# dual_encoder_shield_3v.net
KiCad netlist of a schematic drawn in EAGLE
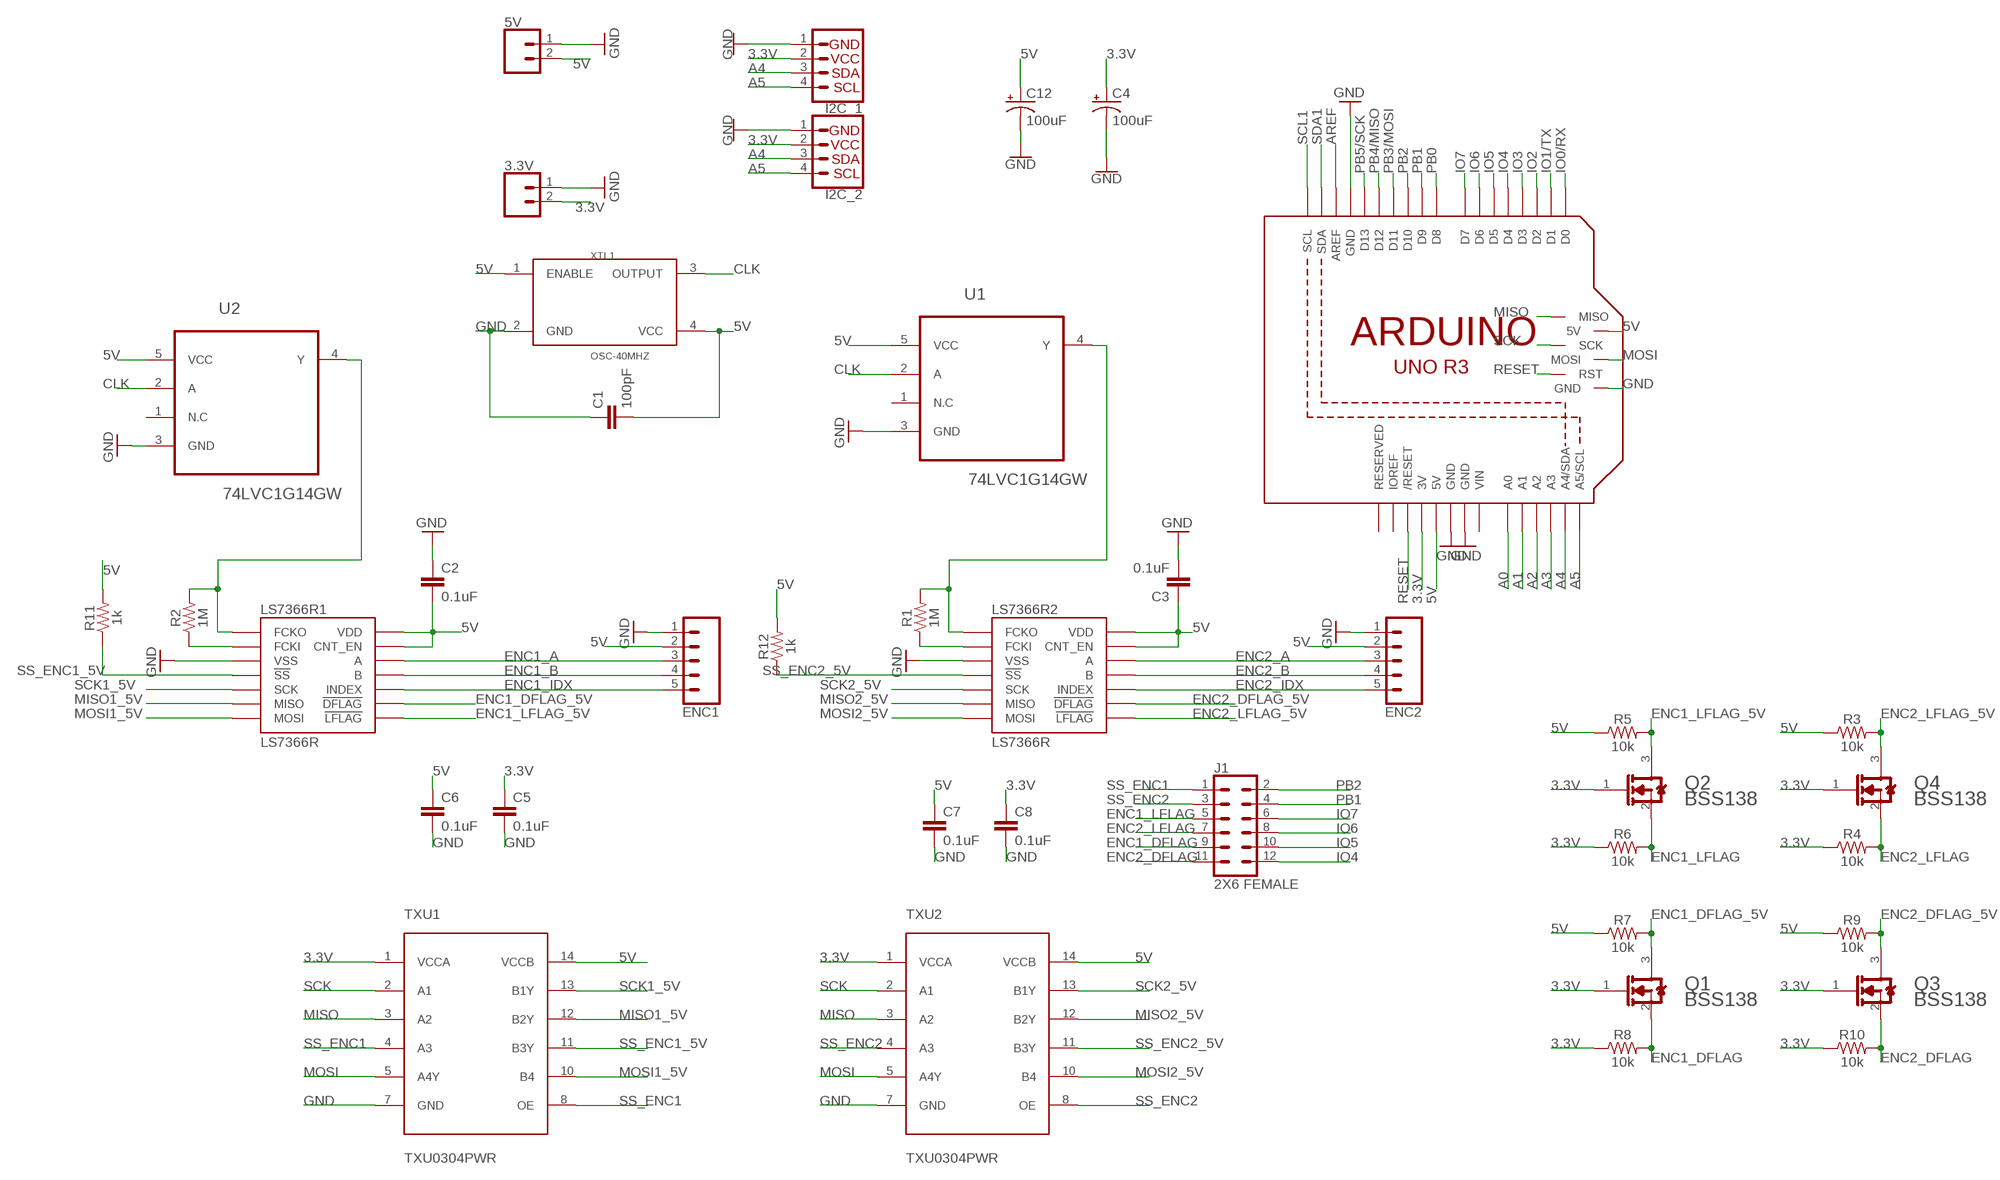
[diagram p0: schematic, sheet 1]

(export (version "E")
  (design (tool "Eeschema 10.0.6"))
  (components
    (comp (ref "3.3V")
      (value "CONN_02-JST-2MM-SMT")
      (footprint "eagle-import:JST-2-SMD")
      (libsource (lib "eagle-import") (part "CONN_02-JST-2MM-SMT"))
    )
    (comp (ref "5V")
      (value "CONN_02-JST-2MM-SMT")
      (footprint "eagle-import:JST-2-SMD")
      (libsource (lib "eagle-import") (part "CONN_02-JST-2MM-SMT"))
    )
    (comp (ref "C1")
      (value "100pF")
      (footprint "eagle-import:0603")
      (libsource (lib "eagle-import") (part "100PF-0603-50V-5%"))
    )
    (comp (ref "C2")
      (value "0.1uF")
      (footprint "eagle-import:0603")
      (libsource (lib "eagle-import") (part "0.1UF-0603-25V-5%"))
    )
    (comp (ref "C3")
      (value "0.1uF")
      (footprint "eagle-import:0603")
      (libsource (lib "eagle-import") (part "0.1UF-0603-25V-5%"))
    )
    (comp (ref "C4")
      (value "100uF")
      (footprint "eagle-import:PANASONIC_D")
      (libsource (lib "eagle-import") (part "100UF-POLAR-25V-20%(ELEC)"))
    )
    (comp (ref "C5")
      (value "0.1uF")
      (footprint "eagle-import:0603")
      (libsource (lib "eagle-import") (part "0.1UF-0603-25V-5%"))
    )
    (comp (ref "C6")
      (value "0.1uF")
      (footprint "eagle-import:0603")
      (libsource (lib "eagle-import") (part "0.1UF-0603-25V-5%"))
    )
    (comp (ref "C7")
      (value "0.1uF")
      (footprint "eagle-import:0603")
      (libsource (lib "eagle-import") (part "0.1UF-0603-25V-5%"))
    )
    (comp (ref "C8")
      (value "0.1uF")
      (footprint "eagle-import:0603")
      (libsource (lib "eagle-import") (part "0.1UF-0603-25V-5%"))
    )
    (comp (ref "C12")
      (value "100uF")
      (footprint "eagle-import:PANASONIC_D")
      (libsource (lib "eagle-import") (part "100UF-POLAR-25V-20%(ELEC)"))
    )
    (comp (ref "ENC1")
      (value "CONN_05")
      (footprint "eagle-import:1X05")
      (libsource (lib "eagle-import") (part "CONN_05"))
    )
    (comp (ref "ENC2")
      (value "CONN_05")
      (footprint "eagle-import:1X05")
      (libsource (lib "eagle-import") (part "CONN_05"))
    )
    (comp (ref "I2C_1")
      (value "QWIIC_CONNECTORJS-1MM")
      (footprint "eagle-import:JST04_1MM_RA")
      (libsource (lib "eagle-import") (part "QWIIC_CONNECTORJS-1MM"))
    )
    (comp (ref "I2C_2")
      (value "QWIIC_CONNECTORJS-1MM")
      (footprint "eagle-import:JST04_1MM_RA")
      (libsource (lib "eagle-import") (part "QWIIC_CONNECTORJS-1MM"))
    )
    (comp (ref "J1")
      (value "2X6 FEMALE")
      (footprint "eagle-import:2X6")
      (libsource (lib "eagle-import") (part "CONN_06X2PTH_FEMALE"))
    )
    (comp (ref "LS7366R1")
      (value "LS7366R")
      (footprint "eagle-import:SOIC14")
      (fields (field (name "MF") "LSI"))
      (libsource (lib "eagle-import") (part "LS7366R"))
    )
    (comp (ref "LS7366R2")
      (value "LS7366R")
      (footprint "eagle-import:SOIC14")
      (fields (field (name "MF") "LSI"))
      (libsource (lib "eagle-import") (part "LS7366R"))
    )
    (comp (ref "M1")
      (value "ARDUINO_R3_ICSP")
      (footprint "eagle-import:ARDUINOR3_ICSP")
      (libsource (lib "eagle-import") (part "ARDUINO_R3_ICSP"))
    )
    (comp (ref "Q1")
      (value "ON_SEMI_BSS138ON_SEMI_BSS138_0_0")
      (footprint "eagle-import:ON_SEMI_BSS138_0")
      (fields
        (field (name "DIGIKEY_PART_NUMBER") "BSS138CT-ND")
        (field (name "MF") "ON Semi")
        (field (name "MOUSER_PART_NUMBER") "512-BSS138")
      )
      (libsource (lib "eagle-import") (part "ON_SEMI_BSS138ON_SEMI_BSS138_0_0"))
    )
    (comp (ref "Q2")
      (value "ON_SEMI_BSS138ON_SEMI_BSS138_0_0")
      (footprint "eagle-import:ON_SEMI_BSS138_0")
      (fields
        (field (name "DIGIKEY_PART_NUMBER") "BSS138CT-ND")
        (field (name "MF") "ON Semi")
        (field (name "MOUSER_PART_NUMBER") "512-BSS138")
      )
      (libsource (lib "eagle-import") (part "ON_SEMI_BSS138ON_SEMI_BSS138_0_0"))
    )
    (comp (ref "Q3")
      (value "ON_SEMI_BSS138ON_SEMI_BSS138_0_0")
      (footprint "eagle-import:ON_SEMI_BSS138_0")
      (fields
        (field (name "DIGIKEY_PART_NUMBER") "BSS138CT-ND")
        (field (name "MF") "ON Semi")
        (field (name "MOUSER_PART_NUMBER") "512-BSS138")
      )
      (libsource (lib "eagle-import") (part "ON_SEMI_BSS138ON_SEMI_BSS138_0_0"))
    )
    (comp (ref "Q4")
      (value "ON_SEMI_BSS138ON_SEMI_BSS138_0_0")
      (footprint "eagle-import:ON_SEMI_BSS138_0")
      (fields
        (field (name "DIGIKEY_PART_NUMBER") "BSS138CT-ND")
        (field (name "MF") "ON Semi")
        (field (name "MOUSER_PART_NUMBER") "512-BSS138")
      )
      (libsource (lib "eagle-import") (part "ON_SEMI_BSS138ON_SEMI_BSS138_0_0"))
    )
    (comp (ref "R1")
      (value "1M")
      (footprint "eagle-import:0603")
      (libsource (lib "eagle-import") (part "1MOHM-0603-1/4W-5%"))
    )
    (comp (ref "R2")
      (value "1M")
      (footprint "eagle-import:0603")
      (libsource (lib "eagle-import") (part "1MOHM-0603-1/4W-5%"))
    )
    (comp (ref "R3")
      (value "10k")
      (footprint "eagle-import:0603")
      (libsource (lib "eagle-import") (part "10KOHM-0603-1/10W-1%"))
    )
    (comp (ref "R4")
      (value "10k")
      (footprint "eagle-import:0603")
      (libsource (lib "eagle-import") (part "10KOHM-0603-1/10W-1%"))
    )
    (comp (ref "R5")
      (value "10k")
      (footprint "eagle-import:0603")
      (libsource (lib "eagle-import") (part "10KOHM-0603-1/10W-1%"))
    )
    (comp (ref "R6")
      (value "10k")
      (footprint "eagle-import:0603")
      (libsource (lib "eagle-import") (part "10KOHM-0603-1/10W-1%"))
    )
    (comp (ref "R7")
      (value "10k")
      (footprint "eagle-import:0603")
      (libsource (lib "eagle-import") (part "10KOHM-0603-1/10W-1%"))
    )
    (comp (ref "R8")
      (value "10k")
      (footprint "eagle-import:0603")
      (libsource (lib "eagle-import") (part "10KOHM-0603-1/10W-1%"))
    )
    (comp (ref "R9")
      (value "10k")
      (footprint "eagle-import:0603")
      (libsource (lib "eagle-import") (part "10KOHM-0603-1/10W-1%"))
    )
    (comp (ref "R10")
      (value "10k")
      (footprint "eagle-import:0603")
      (libsource (lib "eagle-import") (part "10KOHM-0603-1/10W-1%"))
    )
    (comp (ref "R11")
      (value "1k")
      (footprint "eagle-import:0603")
      (libsource (lib "eagle-import") (part "1KOHM-0603-1/10W-1%"))
    )
    (comp (ref "R12")
      (value "1k")
      (footprint "eagle-import:0603")
      (libsource (lib "eagle-import") (part "1KOHM-0603-1/10W-1%"))
    )
    (comp (ref "TXU1")
      (value "TXU0304PWR")
      (footprint "eagle-import:SOP65P640X95-14N")
      (libsource (lib "eagle-import") (part "TXU0304PWR"))
    )
    (comp (ref "TXU2")
      (value "TXU0304PWR")
      (footprint "eagle-import:SOP65P640X95-14N")
      (libsource (lib "eagle-import") (part "TXU0304PWR"))
    )
    (comp (ref "U1")
      (value "74LVC1G14GW")
      (footprint "eagle-import:SOT65P210X110-5N")
      (fields (field (name "MF") "NXP Semiconductors"))
      (libsource (lib "eagle-import") (part "74LVC1G14GW"))
    )
    (comp (ref "U2")
      (value "74LVC1G14GW")
      (footprint "eagle-import:SOT65P210X110-5N")
      (fields (field (name "MF") "NXP Semiconductors"))
      (libsource (lib "eagle-import") (part "74LVC1G14GW"))
    )
    (comp (ref "XTL1")
      (value "OSC-40MHZ")
      (footprint "eagle-import:OSC_CB3LV-5I-50M000000")
      (libsource (lib "eagle-import") (part "OSC-40MHZ"))
    )
  )
  (nets
    (net (code "1") (name "/3.3V") (class "Default")
      (node (ref "3.3V") (pin "2") (pinfunction "1_2") (pintype "passive"))
      (node (ref "C4") (pin "+") (pinfunction "+_+") (pintype "passive"))
      (node (ref "C5") (pin "1") (pinfunction "1_1") (pintype "passive"))
      (node (ref "C8") (pin "1") (pinfunction "1_1") (pintype "passive"))
      (node (ref "I2C_1") (pin "2") (pinfunction "2_2") (pintype "power_in"))
      (node (ref "I2C_2") (pin "2") (pinfunction "2_2") (pintype "power_in"))
      (node (ref "M1") (pin "3V") (pinfunction "3V_3V") (pintype "power_in"))
      (node (ref "Q1") (pin "1") (pinfunction "G_1") (pintype "bidirectional"))
      (node (ref "Q2") (pin "1") (pinfunction "G_1") (pintype "bidirectional"))
      (node (ref "Q3") (pin "1") (pinfunction "G_1") (pintype "bidirectional"))
      (node (ref "Q4") (pin "1") (pinfunction "G_1") (pintype "bidirectional"))
      (node (ref "R10") (pin "1") (pinfunction "1_1") (pintype "passive"))
      (node (ref "R4") (pin "1") (pinfunction "1_1") (pintype "passive"))
      (node (ref "R6") (pin "1") (pinfunction "1_1") (pintype "passive"))
      (node (ref "R8") (pin "1") (pinfunction "1_1") (pintype "passive"))
      (node (ref "TXU1") (pin "1") (pinfunction "VCCA_1") (pintype "bidirectional"))
      (node (ref "TXU2") (pin "1") (pinfunction "VCCA_1") (pintype "bidirectional"))
    )
    (net (code "2") (name "/5V") (class "Default")
      (node (ref "5V") (pin "2") (pinfunction "1_2") (pintype "passive"))
      (node (ref "C1") (pin "2") (pinfunction "2_2") (pintype "passive"))
      (node (ref "C12") (pin "+") (pinfunction "+_+") (pintype "passive"))
      (node (ref "C2") (pin "2") (pinfunction "2_2") (pintype "passive"))
      (node (ref "C3") (pin "1") (pinfunction "1_1") (pintype "passive"))
      (node (ref "C6") (pin "1") (pinfunction "1_1") (pintype "passive"))
      (node (ref "C7") (pin "1") (pinfunction "1_1") (pintype "passive"))
      (node (ref "ENC1") (pin "2") (pinfunction "2_2") (pintype "passive"))
      (node (ref "ENC2") (pin "2") (pinfunction "2_2") (pintype "passive"))
      (node (ref "LS7366R1") (pin "13") (pinfunction "CNT_EN_13") (pintype "bidirectional"))
      (node (ref "LS7366R1") (pin "14") (pinfunction "VDD_14") (pintype "bidirectional"))
      (node (ref "LS7366R2") (pin "13") (pinfunction "CNT_EN_13") (pintype "bidirectional"))
      (node (ref "LS7366R2") (pin "14") (pinfunction "VDD_14") (pintype "bidirectional"))
      (node (ref "M1") (pin "5V") (pinfunction "5V_5V") (pintype "power_in"))
      (node (ref "M1") (pin "5V_ICSP") (pinfunction "5V_5V_ICSP") (pintype "passive"))
      (node (ref "R11") (pin "2") (pinfunction "2_2") (pintype "passive"))
      (node (ref "R12") (pin "2") (pinfunction "2_2") (pintype "passive"))
      (node (ref "R3") (pin "1") (pinfunction "1_1") (pintype "passive"))
      (node (ref "R5") (pin "1") (pinfunction "1_1") (pintype "passive"))
      (node (ref "R7") (pin "1") (pinfunction "1_1") (pintype "passive"))
      (node (ref "R9") (pin "1") (pinfunction "1_1") (pintype "passive"))
      (node (ref "TXU1") (pin "14") (pinfunction "VCCB_14") (pintype "bidirectional"))
      (node (ref "TXU2") (pin "14") (pinfunction "VCCB_14") (pintype "bidirectional"))
      (node (ref "U1") (pin "5") (pinfunction "VCC_5") (pintype "power_in"))
      (node (ref "U2") (pin "5") (pinfunction "VCC_5") (pintype "power_in"))
      (node (ref "XTL1") (pin "1") (pinfunction "ENABLE_1") (pintype "bidirectional"))
      (node (ref "XTL1") (pin "4") (pinfunction "VCC_4") (pintype "bidirectional"))
    )
    (net (code "3") (name "/A0") (class "Default")
      (node (ref "M1") (pin "A0") (pinfunction "A0_A0") (pintype "bidirectional"))
    )
    (net (code "4") (name "/A1") (class "Default")
      (node (ref "M1") (pin "A1") (pinfunction "A1_A1") (pintype "bidirectional"))
    )
    (net (code "5") (name "/A2") (class "Default")
      (node (ref "M1") (pin "A2") (pinfunction "A2_A2") (pintype "bidirectional"))
    )
    (net (code "6") (name "/A3") (class "Default")
      (node (ref "M1") (pin "A3") (pinfunction "A3_A3") (pintype "bidirectional"))
    )
    (net (code "7") (name "/A4") (class "Default")
      (node (ref "I2C_1") (pin "3") (pinfunction "3_3") (pintype "passive"))
      (node (ref "I2C_2") (pin "3") (pinfunction "3_3") (pintype "passive"))
      (node (ref "M1") (pin "A4") (pinfunction "A4/SDA_A4") (pintype "bidirectional"))
    )
    (net (code "8") (name "/A5") (class "Default")
      (node (ref "I2C_1") (pin "4") (pinfunction "4_4") (pintype "passive"))
      (node (ref "I2C_2") (pin "4") (pinfunction "4_4") (pintype "passive"))
      (node (ref "M1") (pin "A5") (pinfunction "A5/SCL_A5") (pintype "bidirectional"))
    )
    (net (code "9") (name "/AREF") (class "Default")
      (node (ref "M1") (pin "AREF") (pinfunction "AREF_AREF") (pintype "bidirectional"))
    )
    (net (code "10") (name "/CLK") (class "Default")
      (node (ref "U1") (pin "2") (pinfunction "A_2") (pintype "input"))
      (node (ref "U2") (pin "2") (pinfunction "A_2") (pintype "input"))
      (node (ref "XTL1") (pin "3") (pinfunction "OUTPUT_3") (pintype "bidirectional"))
    )
    (net (code "11") (name "/ENC1_A") (class "Default")
      (node (ref "ENC1") (pin "3") (pinfunction "3_3") (pintype "passive"))
      (node (ref "LS7366R1") (pin "12") (pinfunction "A_12") (pintype "bidirectional"))
    )
    (net (code "12") (name "/ENC1_B") (class "Default")
      (node (ref "ENC1") (pin "4") (pinfunction "4_4") (pintype "passive"))
      (node (ref "LS7366R1") (pin "11") (pinfunction "B_11") (pintype "bidirectional"))
    )
    (net (code "13") (name "/ENC1_DFLAG") (class "Default")
      (node (ref "J1") (pin "9") (pinfunction "9_9") (pintype "passive"))
      (node (ref "Q1") (pin "2") (pinfunction "S_2") (pintype "bidirectional"))
      (node (ref "R8") (pin "2") (pinfunction "2_2") (pintype "passive"))
    )
    (net (code "14") (name "/ENC1_DFLAG_5V") (class "Default")
      (node (ref "LS7366R1") (pin "9") (pinfunction "~{DFLAG}_9") (pintype "bidirectional"))
      (node (ref "Q1") (pin "3") (pinfunction "D_3") (pintype "bidirectional"))
      (node (ref "R7") (pin "2") (pinfunction "2_2") (pintype "passive"))
    )
    (net (code "15") (name "/ENC1_IDX") (class "Default")
      (node (ref "ENC1") (pin "5") (pinfunction "5_5") (pintype "passive"))
      (node (ref "LS7366R1") (pin "10") (pinfunction "INDEX_10") (pintype "bidirectional"))
    )
    (net (code "16") (name "/ENC1_LFLAG") (class "Default")
      (node (ref "J1") (pin "5") (pinfunction "5_5") (pintype "passive"))
      (node (ref "Q2") (pin "2") (pinfunction "S_2") (pintype "bidirectional"))
      (node (ref "R6") (pin "2") (pinfunction "2_2") (pintype "passive"))
    )
    (net (code "17") (name "/ENC1_LFLAG_5V") (class "Default")
      (node (ref "LS7366R1") (pin "8") (pinfunction "~{LFLAG}_8") (pintype "bidirectional"))
      (node (ref "Q2") (pin "3") (pinfunction "D_3") (pintype "bidirectional"))
      (node (ref "R5") (pin "2") (pinfunction "2_2") (pintype "passive"))
    )
    (net (code "18") (name "/ENC2_A") (class "Default")
      (node (ref "ENC2") (pin "3") (pinfunction "3_3") (pintype "passive"))
      (node (ref "LS7366R2") (pin "12") (pinfunction "A_12") (pintype "bidirectional"))
    )
    (net (code "19") (name "/ENC2_B") (class "Default")
      (node (ref "ENC2") (pin "4") (pinfunction "4_4") (pintype "passive"))
      (node (ref "LS7366R2") (pin "11") (pinfunction "B_11") (pintype "bidirectional"))
    )
    (net (code "20") (name "/ENC2_DFLAG") (class "Default")
      (node (ref "J1") (pin "11") (pinfunction "11_11") (pintype "passive"))
      (node (ref "Q3") (pin "2") (pinfunction "S_2") (pintype "bidirectional"))
      (node (ref "R10") (pin "2") (pinfunction "2_2") (pintype "passive"))
    )
    (net (code "21") (name "/ENC2_DFLAG_5V") (class "Default")
      (node (ref "LS7366R2") (pin "9") (pinfunction "~{DFLAG}_9") (pintype "bidirectional"))
      (node (ref "Q3") (pin "3") (pinfunction "D_3") (pintype "bidirectional"))
      (node (ref "R9") (pin "2") (pinfunction "2_2") (pintype "passive"))
    )
    (net (code "22") (name "/ENC2_IDX") (class "Default")
      (node (ref "ENC2") (pin "5") (pinfunction "5_5") (pintype "passive"))
      (node (ref "LS7366R2") (pin "10") (pinfunction "INDEX_10") (pintype "bidirectional"))
    )
    (net (code "23") (name "/ENC2_LFLAG") (class "Default")
      (node (ref "J1") (pin "7") (pinfunction "7_7") (pintype "passive"))
      (node (ref "Q4") (pin "2") (pinfunction "S_2") (pintype "bidirectional"))
      (node (ref "R4") (pin "2") (pinfunction "2_2") (pintype "passive"))
    )
    (net (code "24") (name "/ENC2_LFLAG_5V") (class "Default")
      (node (ref "LS7366R2") (pin "8") (pinfunction "~{LFLAG}_8") (pintype "bidirectional"))
      (node (ref "Q4") (pin "3") (pinfunction "D_3") (pintype "bidirectional"))
      (node (ref "R3") (pin "2") (pinfunction "2_2") (pintype "passive"))
    )
    (net (code "25") (name "/IO0{slash}RX") (class "Default")
      (node (ref "M1") (pin "D0") (pinfunction "D0_D0") (pintype "bidirectional"))
    )
    (net (code "26") (name "/IO1{slash}TX") (class "Default")
      (node (ref "M1") (pin "D1") (pinfunction "D1_D1") (pintype "bidirectional"))
    )
    (net (code "27") (name "/IO2") (class "Default")
      (node (ref "M1") (pin "D2") (pinfunction "D2_D2") (pintype "bidirectional"))
    )
    (net (code "28") (name "/IO3") (class "Default")
      (node (ref "M1") (pin "D3") (pinfunction "D3_D3") (pintype "bidirectional"))
    )
    (net (code "29") (name "/IO4") (class "Default")
      (node (ref "J1") (pin "12") (pinfunction "12_12") (pintype "passive"))
      (node (ref "M1") (pin "D4") (pinfunction "D4_D4") (pintype "bidirectional"))
    )
    (net (code "30") (name "/IO5") (class "Default")
      (node (ref "J1") (pin "10") (pinfunction "10_10") (pintype "passive"))
      (node (ref "M1") (pin "D5") (pinfunction "D5_D5") (pintype "bidirectional"))
    )
    (net (code "31") (name "/IO6") (class "Default")
      (node (ref "J1") (pin "8") (pinfunction "8_8") (pintype "passive"))
      (node (ref "M1") (pin "D6") (pinfunction "D6_D6") (pintype "bidirectional"))
    )
    (net (code "32") (name "/IO7") (class "Default")
      (node (ref "J1") (pin "6") (pinfunction "6_6") (pintype "passive"))
      (node (ref "M1") (pin "D7") (pinfunction "D7_D7") (pintype "bidirectional"))
    )
    (net (code "33") (name "/MISO") (class "Default")
      (node (ref "M1") (pin "MISO") (pinfunction "MISO_MISO") (pintype "passive"))
      (node (ref "TXU1") (pin "3") (pinfunction "A2_3") (pintype "bidirectional"))
      (node (ref "TXU2") (pin "3") (pinfunction "A2_3") (pintype "bidirectional"))
    )
    (net (code "34") (name "/MISO1_5V") (class "Default")
      (node (ref "LS7366R1") (pin "6") (pinfunction "MISO_6") (pintype "bidirectional"))
      (node (ref "TXU1") (pin "12") (pinfunction "B2Y_12") (pintype "bidirectional"))
    )
    (net (code "35") (name "/MISO2_5V") (class "Default")
      (node (ref "LS7366R2") (pin "6") (pinfunction "MISO_6") (pintype "bidirectional"))
      (node (ref "TXU2") (pin "12") (pinfunction "B2Y_12") (pintype "bidirectional"))
    )
    (net (code "36") (name "/MOSI") (class "Default")
      (node (ref "M1") (pin "MOSI") (pinfunction "MOSI_MOSI") (pintype "passive"))
      (node (ref "TXU1") (pin "5") (pinfunction "A4Y_5") (pintype "bidirectional"))
      (node (ref "TXU2") (pin "5") (pinfunction "A4Y_5") (pintype "bidirectional"))
    )
    (net (code "37") (name "/MOSI1_5V") (class "Default")
      (node (ref "LS7366R1") (pin "7") (pinfunction "MOSI_7") (pintype "bidirectional"))
      (node (ref "TXU1") (pin "10") (pinfunction "B4_10") (pintype "bidirectional"))
    )
    (net (code "38") (name "/MOSI2_5V") (class "Default")
      (node (ref "LS7366R2") (pin "7") (pinfunction "MOSI_7") (pintype "bidirectional"))
      (node (ref "TXU2") (pin "10") (pinfunction "B4_10") (pintype "bidirectional"))
    )
    (net (code "39") (name "/PB0") (class "Default")
      (node (ref "M1") (pin "D8") (pinfunction "D8_D8") (pintype "bidirectional"))
    )
    (net (code "40") (name "/PB1") (class "Default")
      (node (ref "J1") (pin "4") (pinfunction "4_4") (pintype "passive"))
      (node (ref "M1") (pin "D9") (pinfunction "D9_D9") (pintype "bidirectional"))
    )
    (net (code "41") (name "/PB2") (class "Default")
      (node (ref "J1") (pin "2") (pinfunction "2_2") (pintype "passive"))
      (node (ref "M1") (pin "D10") (pinfunction "D10_D10") (pintype "bidirectional"))
    )
    (net (code "42") (name "/PB3{slash}MOSI") (class "Default")
      (node (ref "M1") (pin "D11") (pinfunction "D11_D11") (pintype "bidirectional"))
    )
    (net (code "43") (name "/PB4{slash}MISO") (class "Default")
      (node (ref "M1") (pin "D12") (pinfunction "D12_D12") (pintype "bidirectional"))
    )
    (net (code "44") (name "/PB5{slash}SCK") (class "Default")
      (node (ref "M1") (pin "D13") (pinfunction "D13_D13") (pintype "bidirectional"))
    )
    (net (code "45") (name "/RESET") (class "Default")
      (node (ref "M1") (pin "RESET") (pinfunction "/RESET_RESET") (pintype "bidirectional"))
      (node (ref "M1") (pin "RESET_ICSP") (pinfunction "RST_RESET_ICSP") (pintype "passive"))
    )
    (net (code "46") (name "/SCK") (class "Default")
      (node (ref "M1") (pin "SCK") (pinfunction "SCK_SCK") (pintype "passive"))
      (node (ref "TXU1") (pin "2") (pinfunction "A1_2") (pintype "bidirectional"))
      (node (ref "TXU2") (pin "2") (pinfunction "A1_2") (pintype "bidirectional"))
    )
    (net (code "47") (name "/SCK1_5V") (class "Default")
      (node (ref "LS7366R1") (pin "5") (pinfunction "SCK_5") (pintype "bidirectional"))
      (node (ref "TXU1") (pin "13") (pinfunction "B1Y_13") (pintype "bidirectional"))
    )
    (net (code "48") (name "/SCK2_5V") (class "Default")
      (node (ref "LS7366R2") (pin "5") (pinfunction "SCK_5") (pintype "bidirectional"))
      (node (ref "TXU2") (pin "13") (pinfunction "B1Y_13") (pintype "bidirectional"))
    )
    (net (code "49") (name "/SCL1") (class "Default")
      (node (ref "M1") (pin "SCL") (pinfunction "SCL_SCL") (pintype "bidirectional"))
    )
    (net (code "50") (name "/SDA1") (class "Default")
      (node (ref "M1") (pin "SDA") (pinfunction "SDA_SDA") (pintype "bidirectional"))
    )
    (net (code "51") (name "/SS_ENC1") (class "Default")
      (node (ref "J1") (pin "1") (pinfunction "1_1") (pintype "passive"))
      (node (ref "TXU1") (pin "4") (pinfunction "A3_4") (pintype "bidirectional"))
      (node (ref "TXU1") (pin "8") (pinfunction "OE_8") (pintype "bidirectional"))
    )
    (net (code "52") (name "/SS_ENC1_5V") (class "Default")
      (node (ref "LS7366R1") (pin "4") (pinfunction "~{SS}_4") (pintype "bidirectional"))
      (node (ref "R11") (pin "1") (pinfunction "1_1") (pintype "passive"))
      (node (ref "TXU1") (pin "11") (pinfunction "B3Y_11") (pintype "bidirectional"))
    )
    (net (code "53") (name "/SS_ENC2") (class "Default")
      (node (ref "J1") (pin "3") (pinfunction "3_3") (pintype "passive"))
      (node (ref "TXU2") (pin "4") (pinfunction "A3_4") (pintype "bidirectional"))
      (node (ref "TXU2") (pin "8") (pinfunction "OE_8") (pintype "bidirectional"))
    )
    (net (code "54") (name "/SS_ENC2_5V") (class "Default")
      (node (ref "LS7366R2") (pin "4") (pinfunction "~{SS}_4") (pintype "bidirectional"))
      (node (ref "R12") (pin "1") (pinfunction "1_1") (pintype "passive"))
      (node (ref "TXU2") (pin "11") (pinfunction "B3Y_11") (pintype "bidirectional"))
    )
    (net (code "55") (name "/VIN") (class "Default")
      (node (ref "M1") (pin "VIN") (pinfunction "VIN_VIN") (pintype "power_in"))
    )
    (net (code "56") (name "GND") (class "Default")
      (node (ref "3.3V") (pin "1") (pinfunction "2_1") (pintype "passive"))
      (node (ref "5V") (pin "1") (pinfunction "2_1") (pintype "passive"))
      (node (ref "C1") (pin "1") (pinfunction "1_1") (pintype "passive"))
      (node (ref "C12") (pin "-") (pinfunction "-_-") (pintype "passive"))
      (node (ref "C2") (pin "1") (pinfunction "1_1") (pintype "passive"))
      (node (ref "C3") (pin "2") (pinfunction "2_2") (pintype "passive"))
      (node (ref "C4") (pin "-") (pinfunction "-_-") (pintype "passive"))
      (node (ref "C5") (pin "2") (pinfunction "2_2") (pintype "passive"))
      (node (ref "C6") (pin "2") (pinfunction "2_2") (pintype "passive"))
      (node (ref "C7") (pin "2") (pinfunction "2_2") (pintype "passive"))
      (node (ref "C8") (pin "2") (pinfunction "2_2") (pintype "passive"))
      (node (ref "ENC1") (pin "1") (pinfunction "1_1") (pintype "passive"))
      (node (ref "ENC2") (pin "1") (pinfunction "1_1") (pintype "passive"))
      (node (ref "I2C_1") (pin "1") (pinfunction "1_1") (pintype "power_in"))
      (node (ref "I2C_2") (pin "1") (pinfunction "1_1") (pintype "power_in"))
      (node (ref "LS7366R1") (pin "3") (pinfunction "VSS_3") (pintype "bidirectional"))
      (node (ref "LS7366R2") (pin "3") (pinfunction "VSS_3") (pintype "bidirectional"))
      (node (ref "M1") (pin "GND") (pinfunction "GND_GND") (pintype "power_in"))
      (node (ref "M1") (pin "GND@1") (pinfunction "GND_GND@1") (pintype "power_in"))
      (node (ref "M1") (pin "GND@2") (pinfunction "GND_GND@2") (pintype "passive"))
      (node (ref "M1") (pin "GND@3") (pinfunction "GND_GND@3") (pintype "power_in"))
      (node (ref "TXU1") (pin "7") (pinfunction "GND_7") (pintype "bidirectional"))
      (node (ref "TXU2") (pin "7") (pinfunction "GND_7") (pintype "bidirectional"))
      (node (ref "U1") (pin "3") (pinfunction "GND_3") (pintype "passive"))
      (node (ref "U2") (pin "3") (pinfunction "GND_3") (pintype "passive"))
      (node (ref "XTL1") (pin "2") (pinfunction "GND_2") (pintype "bidirectional"))
    )
    (net (code "57") (name "Net-(LS7366R1-FCKI)") (class "Default")
      (node (ref "LS7366R1") (pin "2") (pinfunction "FCKI_2") (pintype "bidirectional"))
      (node (ref "R2") (pin "1") (pinfunction "1_1") (pintype "passive"))
    )
    (net (code "58") (name "Net-(LS7366R1-FCKO)") (class "Default")
      (node (ref "LS7366R1") (pin "1") (pinfunction "FCKO_1") (pintype "bidirectional"))
      (node (ref "R2") (pin "2") (pinfunction "2_2") (pintype "passive"))
      (node (ref "U2") (pin "4") (pinfunction "Y_4") (pintype "output"))
    )
    (net (code "59") (name "Net-(LS7366R2-FCKI)") (class "Default")
      (node (ref "LS7366R2") (pin "2") (pinfunction "FCKI_2") (pintype "bidirectional"))
      (node (ref "R1") (pin "1") (pinfunction "1_1") (pintype "passive"))
    )
    (net (code "60") (name "Net-(LS7366R2-FCKO)") (class "Default")
      (node (ref "LS7366R2") (pin "1") (pinfunction "FCKO_1") (pintype "bidirectional"))
      (node (ref "R1") (pin "2") (pinfunction "2_2") (pintype "passive"))
      (node (ref "U1") (pin "4") (pinfunction "Y_4") (pintype "output"))
    )
    (net (code "61") (name "unconnected-(M1-PadIOREF)") (class "Default")
      (node (ref "M1") (pin "IOREF") (pinfunction "IOREF_IOREF") (pintype "output"))
    )
    (net (code "62") (name "unconnected-(M1-PadRESERVED)") (class "Default")
      (node (ref "M1") (pin "RESERVED") (pinfunction "RESERVED_RESERVED") (pintype "no_connect"))
    )
    (net (code "63") (name "unconnected-(U1-N.C-Pad1)") (class "Default")
      (node (ref "U1") (pin "1") (pinfunction "N.C_1") (pintype "no_connect"))
    )
    (net (code "64") (name "unconnected-(U2-N.C-Pad1)") (class "Default")
      (node (ref "U2") (pin "1") (pinfunction "N.C_1") (pintype "no_connect"))
    )
  )
)
